# AMU-S29-V00-PDOCShutdownRelay.net
KiCad netlist of a schematic drawn in Altium Designer
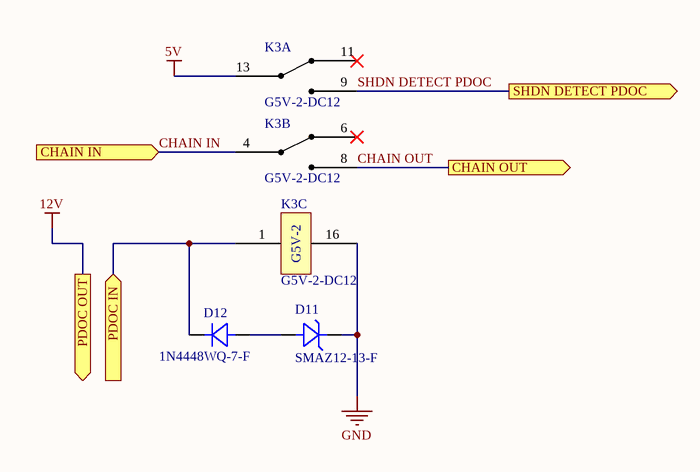
[diagram p0: AMU-S29-V00-PDOCShutdownRelay.SchDoc]

(export (version "E")
  (design (tool "Eeschema 10.0.6"))
  (components
    (comp (ref "D11")
      (value "SMAZ12-13-F")
      (footprint "SMA")
      (description "Zener Diode 12V 1W ±5% Surface Mount SMA")
      (fields (field (name "MANUFACTURER") "ON Semiconductor") (field (name "MPN") "MM3Z56VB"))
      (libsource (lib "QUTMS_DiodeLibrary") (part "SMAZ12-13-F"))
    )
    (comp (ref "D12")
      (value "1N4448WQ-7-F")
      (footprint "SMA")
      (description "Diode, SMD, 75V, 5%, 250mA, SOD123")
      (fields
        (field (name "MANUFACTURER") "ON Semiconductor / Fairchild")
        (field (name "MANUFACTURER PART NUMBER") "1N914BWS")
      )
      (libsource (lib "QUTMS_DiodeLibrary") (part "1N4448WQ-7-F"))
    )
    (comp (ref "K3")
      (value "G5V-2-DC12")
      (footprint "G5V-2")
      (description "General Purpose Relay DPDT (2 Form C) Through Hole, 12V, 2A")
      (libsource (lib "QUTMS_RelayLibrary") (part "G5V-2-DC12"))
    )
  )
  (nets
    (net (code "1") (name "/CHAIN IN") (class "Default")
      (node (ref "K3") (pin "4") (pinfunction "4_4") (pintype "passive"))
    )
    (net (code "2") (name "/CHAIN OUT") (class "Default")
      (node (ref "K3") (pin "8") (pinfunction "8_8") (pintype "passive"))
    )
    (net (code "3") (name "/PDOC IN") (class "Default")
      (node (ref "D12") (pin "K") (pinfunction "Cathode_K") (pintype "passive"))
      (node (ref "K3") (pin "1") (pinfunction "1_1") (pintype "passive"))
    )
    (net (code "4") (name "/SHDN DETECT PDOC") (class "Default")
      (node (ref "K3") (pin "9") (pinfunction "9_9") (pintype "passive"))
    )
    (net (code "5") (name "5V") (class "Default")
      (node (ref "K3") (pin "13") (pinfunction "13_13") (pintype "passive"))
    )
    (net (code "7") (name "GND") (class "Default")
      (node (ref "D11") (pin "K") (pinfunction "Cathode_K") (pintype "passive"))
      (node (ref "K3") (pin "16") (pinfunction "16_16") (pintype "passive"))
    )
    (net (code "8") (name "Net-(D11-Anode)") (class "Default")
      (node (ref "D11") (pin "A") (pinfunction "Anode_A") (pintype "passive"))
      (node (ref "D12") (pin "A") (pinfunction "Anode_A") (pintype "passive"))
    )
    (net (code "9") (name "unconnected-(K3-Pad6)") (class "Default")
      (node (ref "K3") (pin "6") (pinfunction "6_6") (pintype "passive+no_connect"))
    )
    (net (code "10") (name "unconnected-(K3-Pad11)") (class "Default")
      (node (ref "K3") (pin "11") (pinfunction "11_11") (pintype "passive+no_connect"))
    )
  )
)
